# bigSevenV2.net
KiCad netlist of a schematic drawn in EAGLE
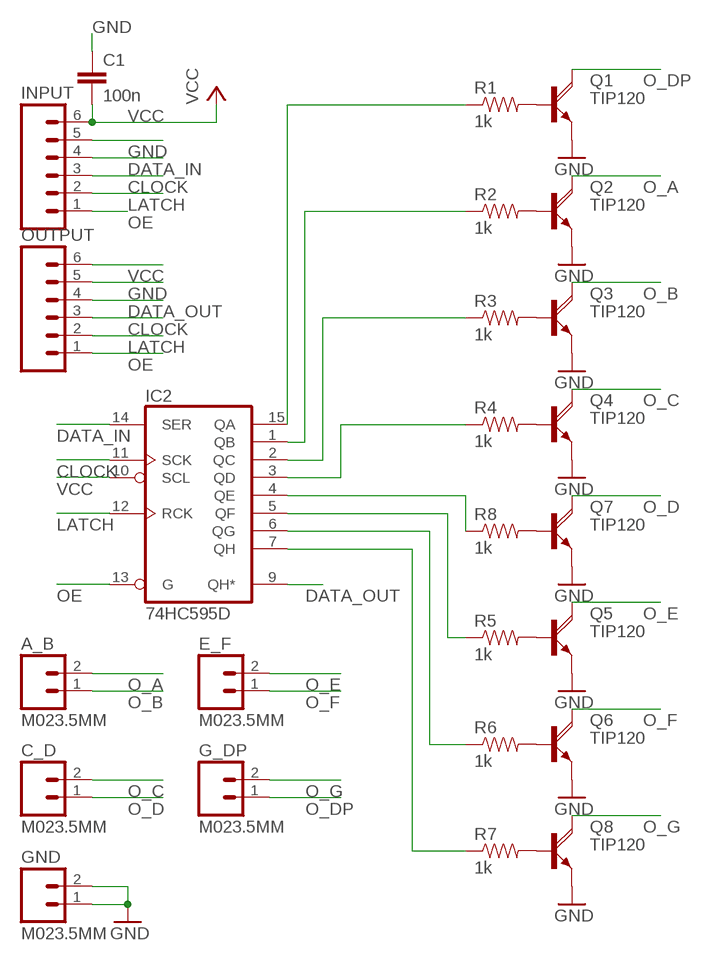
[diagram p0: schematic, sheet 1]

(export (version "E")
  (design (tool "Eeschema 10.0.6"))
  (components
    (comp (ref "A_B")
      (value "M023.5MM")
      (footprint "eagle-import:SCREWTERMINAL-3.5MM-2")
      (libsource (lib "eagle-import") (part "M023.5MM"))
    )
    (comp (ref "C1")
      (value "100n")
      (footprint "eagle-import:0805")
      (libsource (lib "eagle-import") (part "CAP0805"))
    )
    (comp (ref "C_D")
      (value "M023.5MM")
      (footprint "eagle-import:SCREWTERMINAL-3.5MM-2")
      (libsource (lib "eagle-import") (part "M023.5MM"))
    )
    (comp (ref "E_F")
      (value "M023.5MM")
      (footprint "eagle-import:SCREWTERMINAL-3.5MM-2")
      (libsource (lib "eagle-import") (part "M023.5MM"))
    )
    (comp (ref "GND")
      (value "M023.5MM")
      (footprint "eagle-import:SCREWTERMINAL-3.5MM-2")
      (libsource (lib "eagle-import") (part "M023.5MM"))
    )
    (comp (ref "G_DP")
      (value "M023.5MM")
      (footprint "eagle-import:SCREWTERMINAL-3.5MM-2")
      (libsource (lib "eagle-import") (part "M023.5MM"))
    )
    (comp (ref "IC2")
      (value "74HC595D")
      (footprint "eagle-import:SO16")
      (libsource (lib "eagle-import") (part "74595DHC"))
    )
    (comp (ref "INPUT")
      (value "M06LONGPADS")
      (footprint "eagle-import:1X06_LONGPADS")
      (libsource (lib "eagle-import") (part "M06LONGPADS"))
    )
    (comp (ref "OUTPUT")
      (value "M06LONGPADS")
      (footprint "eagle-import:1X06_LONGPADS")
      (libsource (lib "eagle-import") (part "M06LONGPADS"))
    )
    (comp (ref "Q1")
      (value "TIP120")
      (footprint "eagle-import:TO220AH")
      (libsource (lib "eagle-import") (part "TIP120"))
    )
    (comp (ref "Q2")
      (value "TIP120")
      (footprint "eagle-import:TO220AH")
      (libsource (lib "eagle-import") (part "TIP120"))
    )
    (comp (ref "Q3")
      (value "TIP120")
      (footprint "eagle-import:TO220AH")
      (libsource (lib "eagle-import") (part "TIP120"))
    )
    (comp (ref "Q4")
      (value "TIP120")
      (footprint "eagle-import:TO220AH")
      (libsource (lib "eagle-import") (part "TIP120"))
    )
    (comp (ref "Q5")
      (value "TIP120")
      (footprint "eagle-import:TO220AH")
      (libsource (lib "eagle-import") (part "TIP120"))
    )
    (comp (ref "Q6")
      (value "TIP120")
      (footprint "eagle-import:TO220AH")
      (libsource (lib "eagle-import") (part "TIP120"))
    )
    (comp (ref "Q7")
      (value "TIP120")
      (footprint "eagle-import:TO220AH")
      (libsource (lib "eagle-import") (part "TIP120"))
    )
    (comp (ref "Q8")
      (value "TIP120")
      (footprint "eagle-import:TO220AH")
      (libsource (lib "eagle-import") (part "TIP120"))
    )
    (comp (ref "R1")
      (value "1k")
      (footprint "eagle-import:0805")
      (libsource (lib "eagle-import") (part "RESISTOR0805-RES"))
    )
    (comp (ref "R2")
      (value "1k")
      (footprint "eagle-import:0805")
      (libsource (lib "eagle-import") (part "RESISTOR0805-RES"))
    )
    (comp (ref "R3")
      (value "1k")
      (footprint "eagle-import:0805")
      (libsource (lib "eagle-import") (part "RESISTOR0805-RES"))
    )
    (comp (ref "R4")
      (value "1k")
      (footprint "eagle-import:0805")
      (libsource (lib "eagle-import") (part "RESISTOR0805-RES"))
    )
    (comp (ref "R5")
      (value "1k")
      (footprint "eagle-import:0805")
      (libsource (lib "eagle-import") (part "RESISTOR0805-RES"))
    )
    (comp (ref "R6")
      (value "1k")
      (footprint "eagle-import:0805")
      (libsource (lib "eagle-import") (part "RESISTOR0805-RES"))
    )
    (comp (ref "R7")
      (value "1k")
      (footprint "eagle-import:0805")
      (libsource (lib "eagle-import") (part "RESISTOR0805-RES"))
    )
    (comp (ref "R8")
      (value "1k")
      (footprint "eagle-import:0805")
      (libsource (lib "eagle-import") (part "RESISTOR0805-RES"))
    )
  )
  (nets
    (net (code "1") (name "/CLOCK") (class "Default")
      (node (ref "IC2") (pin "11") (pinfunction "SCK_11") (pintype "input"))
      (node (ref "INPUT") (pin "3") (pinfunction "3_3") (pintype "passive"))
      (node (ref "OUTPUT") (pin "3") (pinfunction "3_3") (pintype "passive"))
    )
    (net (code "2") (name "/DATA_IN") (class "Default")
      (node (ref "IC2") (pin "14") (pinfunction "SER_14") (pintype "input"))
      (node (ref "INPUT") (pin "4") (pinfunction "4_4") (pintype "passive"))
    )
    (net (code "3") (name "/DATA_OUT") (class "Default")
      (node (ref "IC2") (pin "9") (pinfunction "QH*_9") (pintype "tri_state"))
      (node (ref "OUTPUT") (pin "4") (pinfunction "4_4") (pintype "passive"))
    )
    (net (code "4") (name "/LATCH") (class "Default")
      (node (ref "IC2") (pin "12") (pinfunction "RCK_12") (pintype "input"))
      (node (ref "INPUT") (pin "2") (pinfunction "2_2") (pintype "passive"))
      (node (ref "OUTPUT") (pin "2") (pinfunction "2_2") (pintype "passive"))
    )
    (net (code "5") (name "/OE") (class "Default")
      (node (ref "IC2") (pin "13") (pinfunction "G_13") (pintype "input"))
      (node (ref "INPUT") (pin "1") (pinfunction "1_1") (pintype "passive"))
      (node (ref "OUTPUT") (pin "1") (pinfunction "1_1") (pintype "passive"))
    )
    (net (code "6") (name "/O_A") (class "Default")
      (node (ref "A_B") (pin "2") (pinfunction "2_2") (pintype "passive"))
      (node (ref "Q2") (pin "C") (pinfunction "C_C") (pintype "passive"))
    )
    (net (code "7") (name "/O_B") (class "Default")
      (node (ref "A_B") (pin "1") (pinfunction "1_1") (pintype "passive"))
      (node (ref "Q3") (pin "C") (pinfunction "C_C") (pintype "passive"))
    )
    (net (code "8") (name "/O_C") (class "Default")
      (node (ref "C_D") (pin "2") (pinfunction "2_2") (pintype "passive"))
      (node (ref "Q4") (pin "C") (pinfunction "C_C") (pintype "passive"))
    )
    (net (code "9") (name "/O_D") (class "Default")
      (node (ref "C_D") (pin "1") (pinfunction "1_1") (pintype "passive"))
      (node (ref "Q7") (pin "C") (pinfunction "C_C") (pintype "passive"))
    )
    (net (code "10") (name "/O_DP") (class "Default")
      (node (ref "G_DP") (pin "1") (pinfunction "1_1") (pintype "passive"))
      (node (ref "Q1") (pin "C") (pinfunction "C_C") (pintype "passive"))
    )
    (net (code "11") (name "/O_E") (class "Default")
      (node (ref "E_F") (pin "2") (pinfunction "2_2") (pintype "passive"))
      (node (ref "Q5") (pin "C") (pinfunction "C_C") (pintype "passive"))
    )
    (net (code "12") (name "/O_F") (class "Default")
      (node (ref "E_F") (pin "1") (pinfunction "1_1") (pintype "passive"))
      (node (ref "Q6") (pin "C") (pinfunction "C_C") (pintype "passive"))
    )
    (net (code "13") (name "/O_G") (class "Default")
      (node (ref "G_DP") (pin "2") (pinfunction "2_2") (pintype "passive"))
      (node (ref "Q8") (pin "C") (pinfunction "C_C") (pintype "passive"))
    )
    (net (code "14") (name "GND") (class "Default")
      (node (ref "C1") (pin "1") (pinfunction "1_1") (pintype "passive"))
      (node (ref "GND") (pin "1") (pinfunction "1_1") (pintype "passive"))
      (node (ref "GND") (pin "2") (pinfunction "2_2") (pintype "passive"))
      (node (ref "INPUT") (pin "5") (pinfunction "5_5") (pintype "passive"))
      (node (ref "OUTPUT") (pin "5") (pinfunction "5_5") (pintype "passive"))
      (node (ref "Q1") (pin "E") (pinfunction "E_E") (pintype "passive"))
      (node (ref "Q2") (pin "E") (pinfunction "E_E") (pintype "passive"))
      (node (ref "Q3") (pin "E") (pinfunction "E_E") (pintype "passive"))
      (node (ref "Q4") (pin "E") (pinfunction "E_E") (pintype "passive"))
      (node (ref "Q5") (pin "E") (pinfunction "E_E") (pintype "passive"))
      (node (ref "Q6") (pin "E") (pinfunction "E_E") (pintype "passive"))
      (node (ref "Q7") (pin "E") (pinfunction "E_E") (pintype "passive"))
      (node (ref "Q8") (pin "E") (pinfunction "E_E") (pintype "passive"))
    )
    (net (code "15") (name "Net-(IC2A-QA)") (class "Default")
      (node (ref "IC2") (pin "15") (pinfunction "QA_15") (pintype "tri_state"))
      (node (ref "R1") (pin "1") (pinfunction "1_1") (pintype "passive"))
    )
    (net (code "16") (name "Net-(IC2A-QB)") (class "Default")
      (node (ref "IC2") (pin "1") (pinfunction "QB_1") (pintype "tri_state"))
      (node (ref "R2") (pin "1") (pinfunction "1_1") (pintype "passive"))
    )
    (net (code "17") (name "Net-(IC2A-QC)") (class "Default")
      (node (ref "IC2") (pin "2") (pinfunction "QC_2") (pintype "tri_state"))
      (node (ref "R3") (pin "1") (pinfunction "1_1") (pintype "passive"))
    )
    (net (code "18") (name "Net-(IC2A-QD)") (class "Default")
      (node (ref "IC2") (pin "3") (pinfunction "QD_3") (pintype "tri_state"))
      (node (ref "R4") (pin "1") (pinfunction "1_1") (pintype "passive"))
    )
    (net (code "19") (name "Net-(IC2A-QE)") (class "Default")
      (node (ref "IC2") (pin "4") (pinfunction "QE_4") (pintype "tri_state"))
      (node (ref "R8") (pin "1") (pinfunction "1_1") (pintype "passive"))
    )
    (net (code "20") (name "Net-(IC2A-QF)") (class "Default")
      (node (ref "IC2") (pin "5") (pinfunction "QF_5") (pintype "tri_state"))
      (node (ref "R5") (pin "1") (pinfunction "1_1") (pintype "passive"))
    )
    (net (code "21") (name "Net-(IC2A-QG)") (class "Default")
      (node (ref "IC2") (pin "6") (pinfunction "QG_6") (pintype "tri_state"))
      (node (ref "R6") (pin "1") (pinfunction "1_1") (pintype "passive"))
    )
    (net (code "22") (name "Net-(IC2A-QH)") (class "Default")
      (node (ref "IC2") (pin "7") (pinfunction "QH_7") (pintype "tri_state"))
      (node (ref "R7") (pin "1") (pinfunction "1_1") (pintype "passive"))
    )
    (net (code "23") (name "Net-(Q1-PadB)") (class "Default")
      (node (ref "Q1") (pin "B") (pinfunction "B_B") (pintype "passive"))
      (node (ref "R1") (pin "2") (pinfunction "2_2") (pintype "passive"))
    )
    (net (code "24") (name "Net-(Q2-PadB)") (class "Default")
      (node (ref "Q2") (pin "B") (pinfunction "B_B") (pintype "passive"))
      (node (ref "R2") (pin "2") (pinfunction "2_2") (pintype "passive"))
    )
    (net (code "25") (name "Net-(Q3-PadB)") (class "Default")
      (node (ref "Q3") (pin "B") (pinfunction "B_B") (pintype "passive"))
      (node (ref "R3") (pin "2") (pinfunction "2_2") (pintype "passive"))
    )
    (net (code "26") (name "Net-(Q4-PadB)") (class "Default")
      (node (ref "Q4") (pin "B") (pinfunction "B_B") (pintype "passive"))
      (node (ref "R4") (pin "2") (pinfunction "2_2") (pintype "passive"))
    )
    (net (code "27") (name "Net-(Q5-PadB)") (class "Default")
      (node (ref "Q5") (pin "B") (pinfunction "B_B") (pintype "passive"))
      (node (ref "R5") (pin "2") (pinfunction "2_2") (pintype "passive"))
    )
    (net (code "28") (name "Net-(Q6-PadB)") (class "Default")
      (node (ref "Q6") (pin "B") (pinfunction "B_B") (pintype "passive"))
      (node (ref "R6") (pin "2") (pinfunction "2_2") (pintype "passive"))
    )
    (net (code "29") (name "Net-(Q7-PadB)") (class "Default")
      (node (ref "Q7") (pin "B") (pinfunction "B_B") (pintype "passive"))
      (node (ref "R8") (pin "2") (pinfunction "2_2") (pintype "passive"))
    )
    (net (code "30") (name "Net-(Q8-PadB)") (class "Default")
      (node (ref "Q8") (pin "B") (pinfunction "B_B") (pintype "passive"))
      (node (ref "R7") (pin "2") (pinfunction "2_2") (pintype "passive"))
    )
    (net (code "31") (name "VCC") (class "Default")
      (node (ref "C1") (pin "2") (pinfunction "2_2") (pintype "passive"))
      (node (ref "IC2") (pin "10") (pinfunction "SCL_10") (pintype "input"))
      (node (ref "INPUT") (pin "6") (pinfunction "6_6") (pintype "passive"))
      (node (ref "OUTPUT") (pin "6") (pinfunction "6_6") (pintype "passive"))
    )
  )
)
